# vxl.net
KiCad netlist of a schematic drawn in Altium Designer
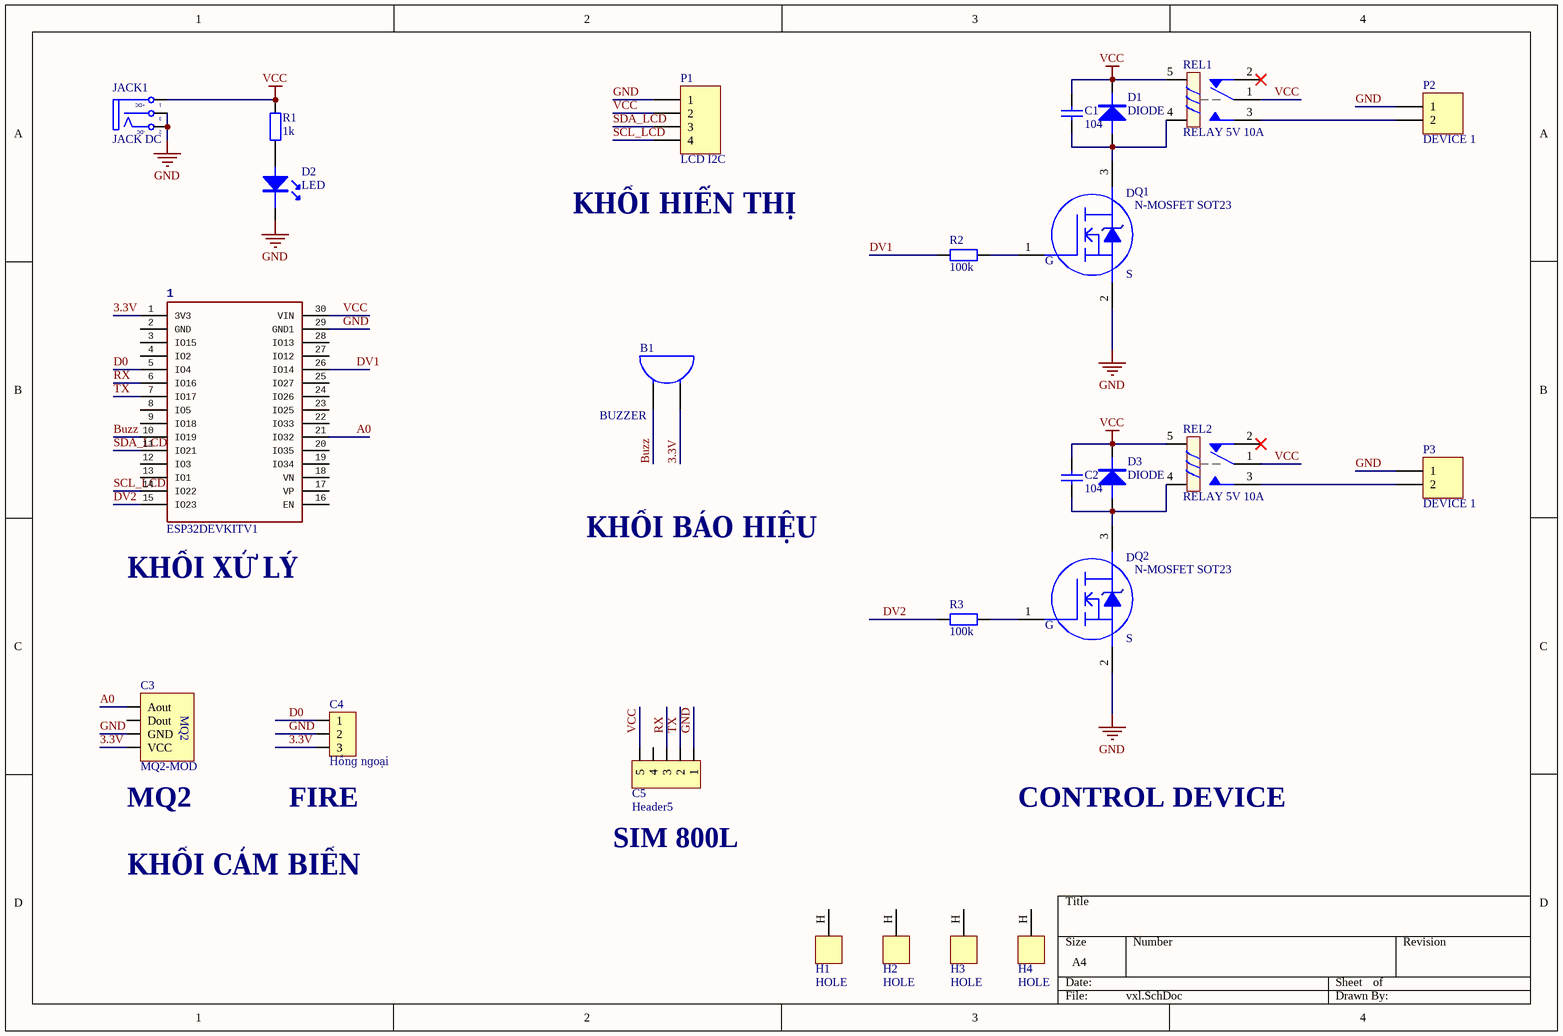
[diagram p0: vxl.SchDoc]

(export (version "E")
  (design (tool "Eeschema 10.0.6"))
  (components
    (comp (ref "1")
      (value "ESP32DEVKITV1")
      (footprint "ESP32-DEVKITV1")
      (libsource (lib "ESP32-DEVKITV1") (part "ESP32DEVKITV1"))
    )
    (comp (ref "B1")
      (value "BUZZER")
      (footprint "SPEAKER")
      (libsource (lib "ThinhNguyenLib") (part "BUZZER"))
    )
    (comp (ref "C1")
      (value "104")
      (footprint "0805 CAP")
      (fields (field (name "PUBLISHER") "Altium Limited"))
      (libsource (lib "THINHDUILIB") (part "CAP CERAMIC"))
    )
    (comp (ref "C2")
      (value "104")
      (footprint "0805 CAP")
      (fields (field (name "PUBLISHER") "Altium Limited"))
      (libsource (lib "THINHDUILIB") (part "CAP CERAMIC"))
    )
    (comp (ref "C3")
      (value "MQ2-MOD")
      (footprint "MQ2-MODULE")
      (fields
        (field (name "MANUFACTURER") "Würth Elektronik eiSos GmbH")
        (field (name "PARTNO") "613004143121")
        (field (name "CREATED BY") "Karrer Zheng")
      )
      (libsource (lib "LIBRARY") (part "MQ2-MOD"))
    )
    (comp (ref "C4")
      (value "Hồng ngoại")
      (footprint "JP3-C1T")
      (description "Header IDC, 3 x 1 Pin Vertical 2.54mm Pitch (Non-Boxed, Male)")
      (fields
        (field (name "MANUFACTURER") "Würth Elektronik eiSos GmbH")
        (field (name "PARTNO") "613002143121")
        (field (name "CREATED BY") "Karrer Zheng")
      )
      (libsource (lib "LIBRARY") (part "Header3"))
    )
    (comp (ref "C5")
      (value "Header5")
      (footprint "HDR1X5")
      (description "Header IDC, 5 x 1 Pin Vertical 2.54mm Pitch (Non-Boxed, Male)")
      (fields
        (field (name "MANUFACTURER") "Würth Elektronik eiSos GmbH")
        (field (name "PARTNO") "613002143121")
        (field (name "CREATED BY") "Karrer Zheng")
      )
      (libsource (lib "LIBRARY") (part "Header5"))
    )
    (comp (ref "D1") (value "DIODE") (footprint "DIODE SMA") (libsource (lib "THINHDUILIB") (part "DIODE")))
    (comp (ref "D2") (value "LED") (footprint "LED SMD 0805") (libsource (lib "THINHDUILIB") (part "LED")))
    (comp (ref "D3") (value "DIODE") (footprint "DIODE SMA") (libsource (lib "THINHDUILIB") (part "DIODE")))
    (comp (ref "H1") (value "HOLE") (footprint "HOLE") (libsource (lib "ThinhNguyenLib") (part "HOLE")))
    (comp (ref "H2") (value "HOLE") (footprint "HOLE") (libsource (lib "ThinhNguyenLib") (part "HOLE")))
    (comp (ref "H3") (value "HOLE") (footprint "HOLE") (libsource (lib "ThinhNguyenLib") (part "HOLE")))
    (comp (ref "H4") (value "HOLE") (footprint "HOLE") (libsource (lib "ThinhNguyenLib") (part "HOLE")))
    (comp (ref "JACK1")
      (value "JACK DC")
      (footprint "JACK DC")
      (libsource (lib "THINHDUILIB") (part "JACK DC"))
    )
    (comp (ref "P1")
      (value "LCD I2C")
      (footprint "HDR1X4")
      (fields (field (name "PUBLISHER") "Altium Limited"))
      (libsource (lib "ThinhNguyenLib") (part "Header 4H"))
    )
    (comp (ref "P2")
      (value "DEVICE 1")
      (footprint "CON 2KF 5.08MM")
      (fields (field (name "PUBLISHER") "Altium Limited"))
      (libsource (lib "THINHDUILIB") (part "Header 2H"))
    )
    (comp (ref "P3")
      (value "DEVICE 1")
      (footprint "CON 2KF 5.08MM")
      (fields (field (name "PUBLISHER") "Altium Limited"))
      (libsource (lib "THINHDUILIB") (part "Header 2H"))
    )
    (comp (ref "Q1")
      (value "N-MOSFET SOT23")
      (footprint "TO-92 - 2N7000")
      (libsource (lib "ThinhNguyenLib") (part "N-MOSFET SOT23"))
    )
    (comp (ref "Q2")
      (value "N-MOSFET SOT23")
      (footprint "TO-92 - 2N7000")
      (libsource (lib "ThinhNguyenLib") (part "N-MOSFET SOT23"))
    )
    (comp (ref "R1")
      (value "1k")
      (footprint "0805 RESISTOR")
      (libsource (lib "THINHDUILIB") (part "RESISTOR"))
    )
    (comp (ref "R2")
      (value "100k")
      (footprint "0805 RESISTOR")
      (libsource (lib "THINHDUILIB") (part "RESISTOR"))
    )
    (comp (ref "R3")
      (value "100k")
      (footprint "0805 RESISTOR")
      (libsource (lib "THINHDUILIB") (part "RESISTOR"))
    )
    (comp (ref "REL1")
      (value "RELAY 5V 10A")
      (footprint "RELAY 5V-10A")
      (libsource (lib "ThinhNguyenLib") (part "RELAY 5V 10A"))
    )
    (comp (ref "REL2")
      (value "RELAY 5V 10A")
      (footprint "RELAY 5V-10A")
      (libsource (lib "ThinhNguyenLib") (part "RELAY 5V 10A"))
    )
  )
  (nets
    (net (code "1") (name "/3.3V") (class "Default")
      (node (ref "1") (pin "1") (pinfunction "3V3_1") (pintype "passive"))
      (node (ref "B1") (pin "2") (pinfunction "B_2") (pintype "passive"))
      (node (ref "C3") (pin "4") (pinfunction "VCC_4") (pintype "passive"))
      (node (ref "C4") (pin "3") (pinfunction "3_3") (pintype "passive"))
    )
    (net (code "2") (name "/A0") (class "Default")
      (node (ref "1") (pin "21") (pinfunction "IO32_21") (pintype "passive"))
      (node (ref "C3") (pin "1") (pinfunction "Aout_1") (pintype "passive"))
    )
    (net (code "3") (name "/Buzz") (class "Default")
      (node (ref "1") (pin "10") (pinfunction "IO19_10") (pintype "passive"))
      (node (ref "B1") (pin "1") (pinfunction "A_1") (pintype "passive"))
    )
    (net (code "4") (name "/D0") (class "Default")
      (node (ref "1") (pin "5") (pinfunction "IO4_5") (pintype "passive"))
      (node (ref "C4") (pin "1") (pinfunction "1_1") (pintype "passive"))
    )
    (net (code "5") (name "/DV1") (class "Default")
      (node (ref "1") (pin "26") (pinfunction "IO14_26") (pintype "passive"))
      (node (ref "R2") (pin "2") (pinfunction "2_2") (pintype "passive"))
    )
    (net (code "6") (name "/DV2") (class "Default")
      (node (ref "1") (pin "15") (pinfunction "IO23_15") (pintype "passive"))
      (node (ref "R3") (pin "2") (pinfunction "2_2") (pintype "passive"))
    )
    (net (code "7") (name "/RX") (class "Default")
      (node (ref "1") (pin "6") (pinfunction "IO16_6") (pintype "passive"))
      (node (ref "C5") (pin "3") (pinfunction "3_3") (pintype "passive"))
    )
    (net (code "8") (name "/SCL_LCD") (class "Default")
      (node (ref "1") (pin "14") (pinfunction "IO22_14") (pintype "passive"))
      (node (ref "P1") (pin "4") (pinfunction "4_4") (pintype "passive"))
    )
    (net (code "9") (name "/SDA_LCD") (class "Default")
      (node (ref "1") (pin "11") (pinfunction "IO21_11") (pintype "passive"))
      (node (ref "P1") (pin "3") (pinfunction "3_3") (pintype "passive"))
    )
    (net (code "10") (name "/TX") (class "Default")
      (node (ref "1") (pin "7") (pinfunction "IO17_7") (pintype "passive"))
      (node (ref "C5") (pin "2") (pinfunction "2_2") (pintype "passive"))
    )
    (net (code "11") (name "GND") (class "Default")
      (node (ref "1") (pin "29") (pinfunction "GND1_29") (pintype "passive"))
      (node (ref "C3") (pin "3") (pinfunction "GND_3") (pintype "passive"))
      (node (ref "C4") (pin "2") (pinfunction "2_2") (pintype "passive"))
      (node (ref "C5") (pin "1") (pinfunction "1_1") (pintype "passive"))
      (node (ref "D2") (pin "2") (pinfunction "2_2") (pintype "passive"))
      (node (ref "JACK1") (pin "2") (pinfunction "TN_2") (pintype "passive"))
      (node (ref "JACK1") (pin "3") (pinfunction "S_3") (pintype "power_in"))
      (node (ref "P1") (pin "1") (pinfunction "1_1") (pintype "passive"))
      (node (ref "P2") (pin "1") (pinfunction "1_1") (pintype "passive"))
      (node (ref "P3") (pin "1") (pinfunction "1_1") (pintype "passive"))
      (node (ref "Q1") (pin "2") (pinfunction "S_2") (pintype "passive"))
      (node (ref "Q2") (pin "2") (pinfunction "S_2") (pintype "passive"))
    )
    (net (code "12") (name "Net-(D2-Pad1)") (class "Default")
      (node (ref "D2") (pin "1") (pinfunction "1_1") (pintype "passive"))
      (node (ref "R1") (pin "1") (pinfunction "1_1") (pintype "passive"))
    )
    (net (code "13") (name "Net-(P2-Pad2)") (class "Default")
      (node (ref "P2") (pin "2") (pinfunction "2_2") (pintype "passive"))
      (node (ref "REL1") (pin "3") (pinfunction "3_3") (pintype "passive"))
    )
    (net (code "14") (name "Net-(P3-Pad2)") (class "Default")
      (node (ref "P3") (pin "2") (pinfunction "2_2") (pintype "passive"))
      (node (ref "REL2") (pin "3") (pinfunction "3_3") (pintype "passive"))
    )
    (net (code "15") (name "Net-(Q1-D)") (class "Default")
      (node (ref "C1") (pin "2") (pinfunction "2_2") (pintype "passive"))
      (node (ref "D1") (pin "1") (pinfunction "1_1") (pintype "passive"))
      (node (ref "Q1") (pin "3") (pinfunction "D_3") (pintype "passive"))
      (node (ref "REL1") (pin "4") (pinfunction "4_4") (pintype "passive"))
    )
    (net (code "16") (name "Net-(Q1-G)") (class "Default")
      (node (ref "Q1") (pin "1") (pinfunction "G_1") (pintype "passive"))
      (node (ref "R2") (pin "1") (pinfunction "1_1") (pintype "passive"))
    )
    (net (code "17") (name "Net-(Q2-D)") (class "Default")
      (node (ref "C2") (pin "2") (pinfunction "2_2") (pintype "passive"))
      (node (ref "D3") (pin "1") (pinfunction "1_1") (pintype "passive"))
      (node (ref "Q2") (pin "3") (pinfunction "D_3") (pintype "passive"))
      (node (ref "REL2") (pin "4") (pinfunction "4_4") (pintype "passive"))
    )
    (net (code "18") (name "Net-(Q2-G)") (class "Default")
      (node (ref "Q2") (pin "1") (pinfunction "G_1") (pintype "passive"))
      (node (ref "R3") (pin "1") (pinfunction "1_1") (pintype "passive"))
    )
    (net (code "19") (name "VCC") (class "Default")
      (node (ref "1") (pin "30") (pinfunction "VIN_30") (pintype "passive"))
      (node (ref "C1") (pin "1") (pinfunction "1_1") (pintype "passive"))
      (node (ref "C2") (pin "1") (pinfunction "1_1") (pintype "passive"))
      (node (ref "C5") (pin "5") (pinfunction "5_5") (pintype "passive"))
      (node (ref "D1") (pin "2") (pinfunction "2_2") (pintype "passive"))
      (node (ref "D3") (pin "2") (pinfunction "2_2") (pintype "passive"))
      (node (ref "JACK1") (pin "1") (pinfunction "T_1") (pintype "passive"))
      (node (ref "P1") (pin "2") (pinfunction "2_2") (pintype "passive"))
      (node (ref "R1") (pin "2") (pinfunction "2_2") (pintype "passive"))
      (node (ref "REL1") (pin "1") (pinfunction "1_1") (pintype "passive"))
      (node (ref "REL1") (pin "5") (pinfunction "5_5") (pintype "passive"))
      (node (ref "REL2") (pin "1") (pinfunction "1_1") (pintype "passive"))
      (node (ref "REL2") (pin "5") (pinfunction "5_5") (pintype "passive"))
    )
    (net (code "20") (name "unconnected-(1-EN-Pad16)") (class "Default")
      (node (ref "1") (pin "16") (pinfunction "EN_16") (pintype "passive"))
    )
    (net (code "21") (name "unconnected-(1-GND-Pad2)") (class "Default")
      (node (ref "1") (pin "2") (pinfunction "GND_2") (pintype "passive"))
    )
    (net (code "22") (name "unconnected-(1-IO1-Pad13)") (class "Default")
      (node (ref "1") (pin "13") (pinfunction "IO1_13") (pintype "passive"))
    )
    (net (code "23") (name "unconnected-(1-IO2-Pad4)") (class "Default")
      (node (ref "1") (pin "4") (pinfunction "IO2_4") (pintype "passive"))
    )
    (net (code "24") (name "unconnected-(1-IO3-Pad12)") (class "Default")
      (node (ref "1") (pin "12") (pinfunction "IO3_12") (pintype "passive"))
    )
    (net (code "25") (name "unconnected-(1-IO5-Pad8)") (class "Default")
      (node (ref "1") (pin "8") (pinfunction "IO5_8") (pintype "passive"))
    )
    (net (code "26") (name "unconnected-(1-IO12-Pad27)") (class "Default")
      (node (ref "1") (pin "27") (pinfunction "IO12_27") (pintype "passive"))
    )
    (net (code "27") (name "unconnected-(1-IO13-Pad28)") (class "Default")
      (node (ref "1") (pin "28") (pinfunction "IO13_28") (pintype "passive"))
    )
    (net (code "28") (name "unconnected-(1-IO15-Pad3)") (class "Default")
      (node (ref "1") (pin "3") (pinfunction "IO15_3") (pintype "passive"))
    )
    (net (code "29") (name "unconnected-(1-IO18-Pad9)") (class "Default")
      (node (ref "1") (pin "9") (pinfunction "IO18_9") (pintype "passive"))
    )
    (net (code "30") (name "unconnected-(1-IO25-Pad23)") (class "Default")
      (node (ref "1") (pin "23") (pinfunction "IO25_23") (pintype "passive"))
    )
    (net (code "31") (name "unconnected-(1-IO26-Pad24)") (class "Default")
      (node (ref "1") (pin "24") (pinfunction "IO26_24") (pintype "passive"))
    )
    (net (code "32") (name "unconnected-(1-IO27-Pad25)") (class "Default")
      (node (ref "1") (pin "25") (pinfunction "IO27_25") (pintype "passive"))
    )
    (net (code "33") (name "unconnected-(1-IO33-Pad22)") (class "Default")
      (node (ref "1") (pin "22") (pinfunction "IO33_22") (pintype "passive"))
    )
    (net (code "34") (name "unconnected-(1-IO34-Pad19)") (class "Default")
      (node (ref "1") (pin "19") (pinfunction "IO34_19") (pintype "passive"))
    )
    (net (code "35") (name "unconnected-(1-IO35-Pad20)") (class "Default")
      (node (ref "1") (pin "20") (pinfunction "IO35_20") (pintype "passive"))
    )
    (net (code "36") (name "unconnected-(1-VN-Pad18)") (class "Default")
      (node (ref "1") (pin "18") (pinfunction "VN_18") (pintype "passive"))
    )
    (net (code "37") (name "unconnected-(1-VP-Pad17)") (class "Default")
      (node (ref "1") (pin "17") (pinfunction "VP_17") (pintype "passive"))
    )
    (net (code "38") (name "unconnected-(C3-Dout-Pad2)") (class "Default")
      (node (ref "C3") (pin "2") (pinfunction "Dout_2") (pintype "passive"))
    )
    (net (code "39") (name "unconnected-(C5-Pad4)") (class "Default")
      (node (ref "C5") (pin "4") (pinfunction "4_4") (pintype "passive"))
    )
    (net (code "40") (name "unconnected-(H1-HOLE-PadH)") (class "Default")
      (node (ref "H1") (pin "H") (pinfunction "HOLE_H") (pintype "passive"))
    )
    (net (code "41") (name "unconnected-(H2-HOLE-PadH)") (class "Default")
      (node (ref "H2") (pin "H") (pinfunction "HOLE_H") (pintype "passive"))
    )
    (net (code "42") (name "unconnected-(H3-HOLE-PadH)") (class "Default")
      (node (ref "H3") (pin "H") (pinfunction "HOLE_H") (pintype "passive"))
    )
    (net (code "43") (name "unconnected-(H4-HOLE-PadH)") (class "Default")
      (node (ref "H4") (pin "H") (pinfunction "HOLE_H") (pintype "passive"))
    )
    (net (code "44") (name "unconnected-(REL1-Pad2)") (class "Default")
      (node (ref "REL1") (pin "2") (pinfunction "2_2") (pintype "passive+no_connect"))
    )
    (net (code "45") (name "unconnected-(REL2-Pad2)") (class "Default")
      (node (ref "REL2") (pin "2") (pinfunction "2_2") (pintype "passive+no_connect"))
    )
  )
)
